# Sheet.net
KiCad netlist of a schematic drawn in Altium Designer
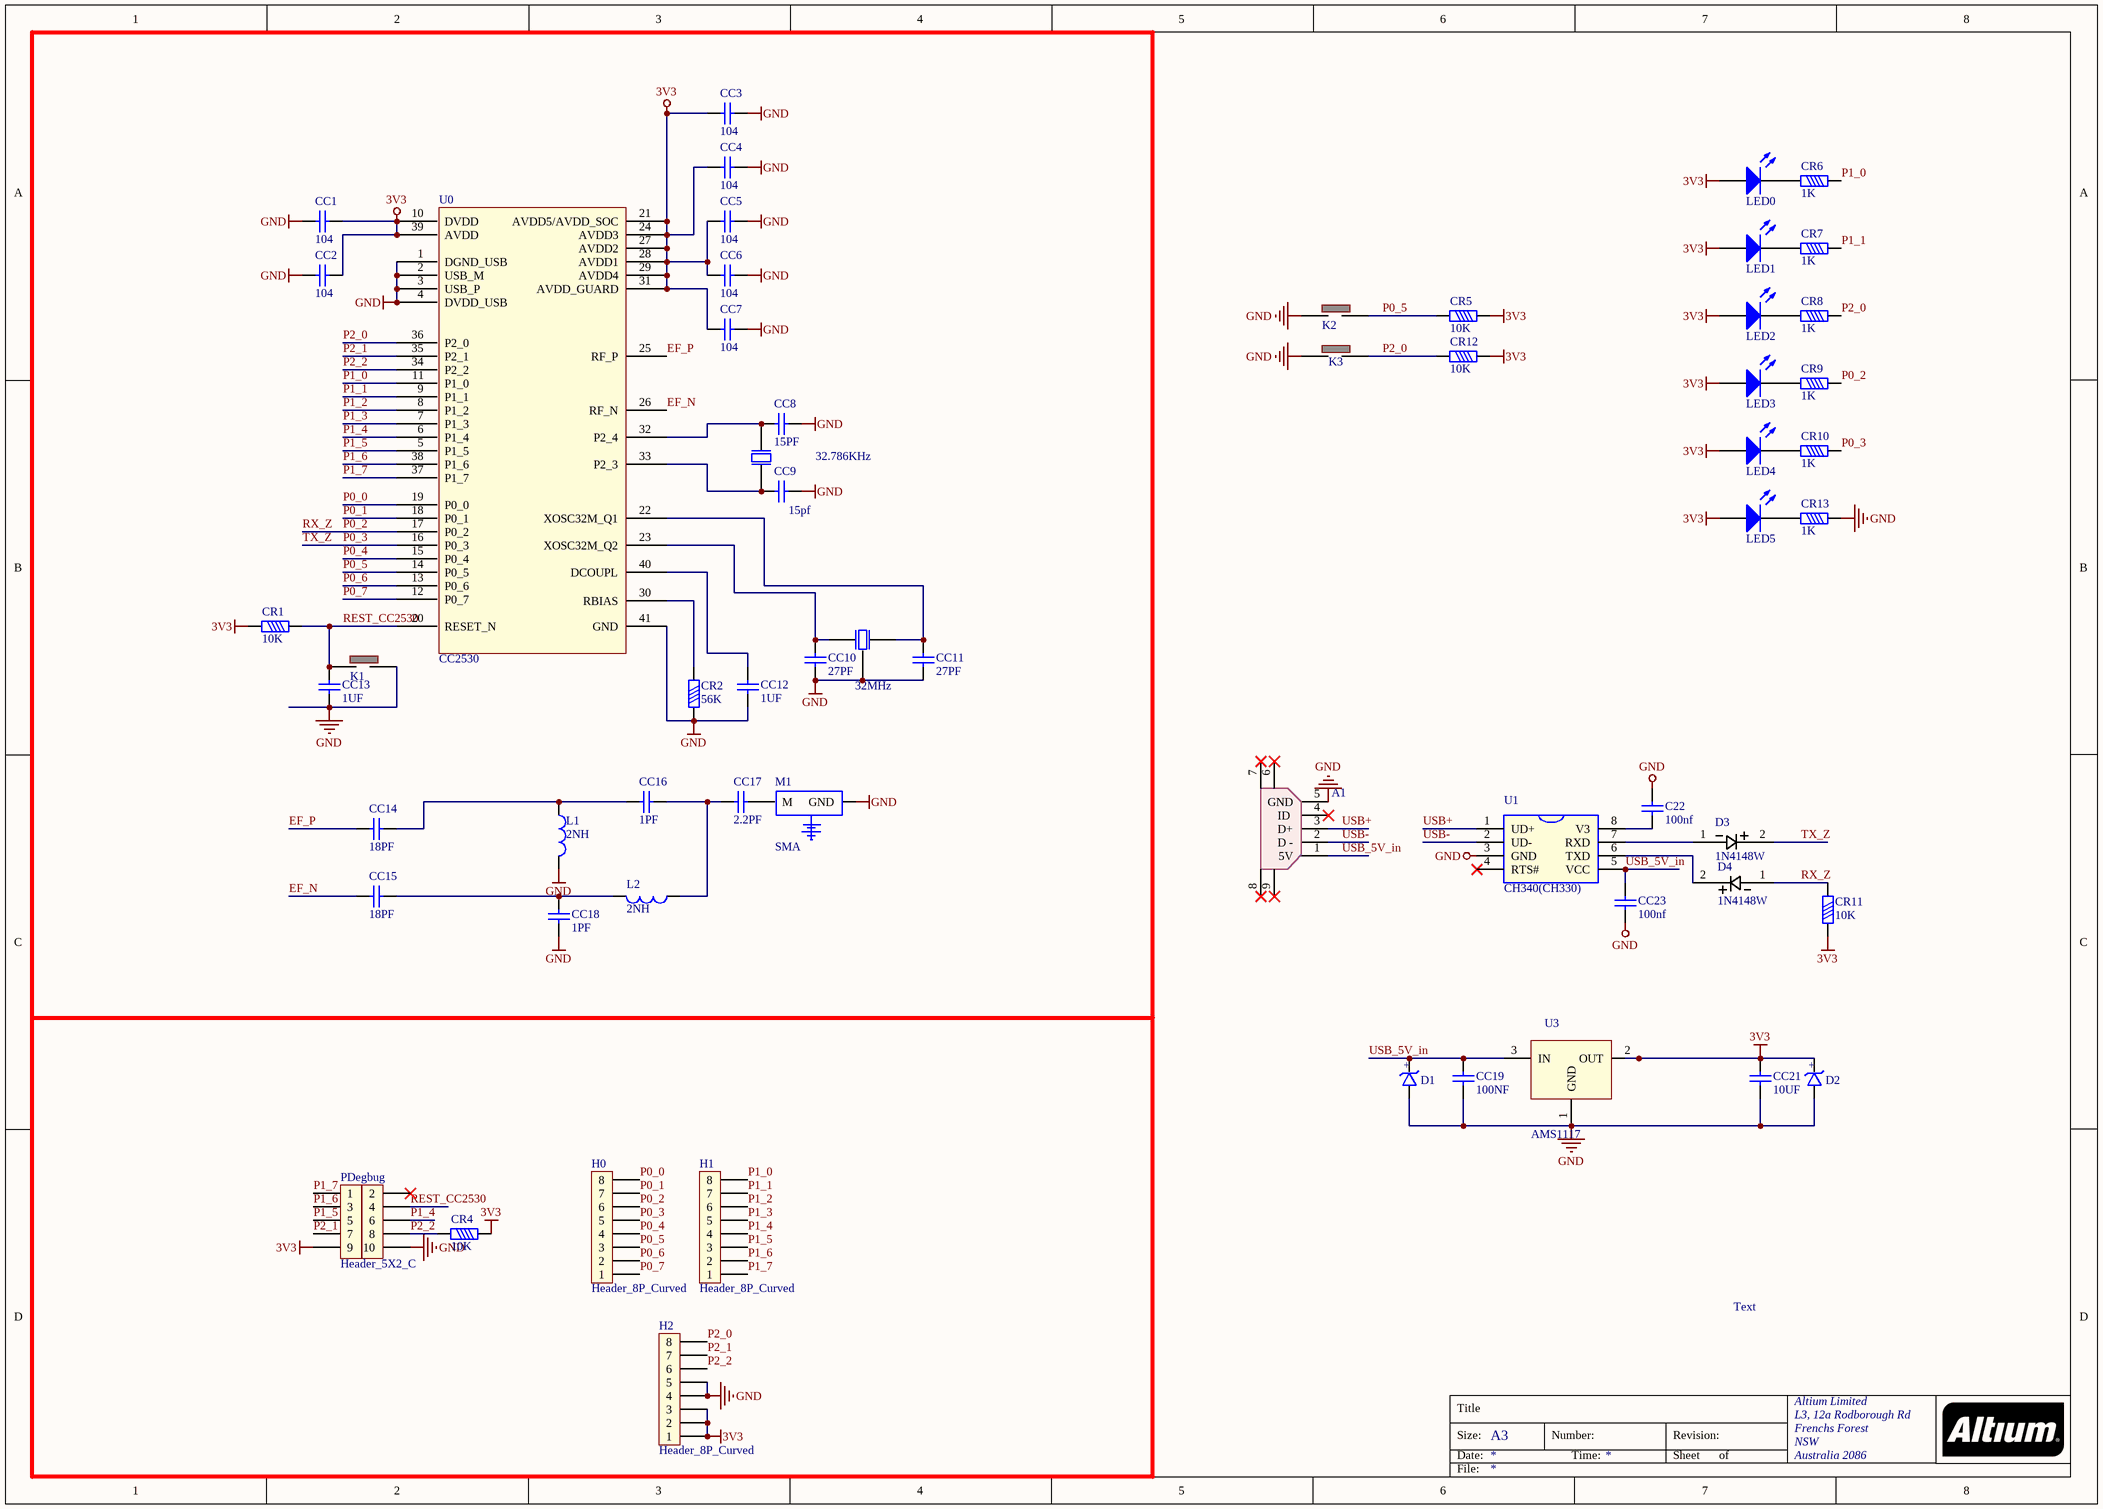
[diagram p0: Sheet.SchDoc]

(export (version "E")
  (design (tool "Eeschema 10.0.6"))
  (components
    (comp (ref "32.786KHz")
      (value "XTAL 3215 32.768kKHz")
      (footprint "T 3215")
      (libsource (lib "tianxiaohua_Schlib") (part "XTAL 3215 32.768kKHz"))
    )
    (comp (ref "32MHz")
      (value "XTAL 3225 8M")
      (footprint "T 3225")
      (libsource (lib "tianxiaohua_Schlib") (part "XTAL 3225 8M"))
    )
    (comp (ref "A1")
      (value "Micro USB")
      (footprint "Micro USB")
      (libsource (lib "tianxiaohua_Schlib") (part "Micro USB"))
    )
    (comp (ref "C22")
      (value "100nf")
      (footprint "CC1608-0603")
      (description "Polarized Capacitor (Radial)")
      (fields (field (name "Comment") "Cap Chip 0603") (field (name "PUBLISHER") "Altium Limited"))
      (libsource (lib "EButterflyIntegratedLibrary") (part "Cap Chip 0603"))
    )
    (comp (ref "CC1")
      (value "104")
      (footprint "CC1608-0603")
      (description "Polarized Capacitor (Radial)")
      (fields (field (name "Comment") "Cap Chip 0603") (field (name "PUBLISHER") "Altium Limited"))
      (libsource (lib "EButterflyIntegratedLibrary") (part "Cap Chip 0603"))
    )
    (comp (ref "CC2")
      (value "104")
      (footprint "CC1608-0603")
      (description "Polarized Capacitor (Radial)")
      (fields (field (name "Comment") "Cap Chip 0603") (field (name "PUBLISHER") "Altium Limited"))
      (libsource (lib "EButterflyIntegratedLibrary") (part "Cap Chip 0603"))
    )
    (comp (ref "CC3")
      (value "104")
      (footprint "CC1608-0603")
      (description "Polarized Capacitor (Radial)")
      (fields (field (name "Comment") "Cap Chip 0603") (field (name "PUBLISHER") "Altium Limited"))
      (libsource (lib "EButterflyIntegratedLibrary") (part "Cap Chip 0603"))
    )
    (comp (ref "CC4")
      (value "104")
      (footprint "CC1608-0603")
      (description "Polarized Capacitor (Radial)")
      (fields (field (name "Comment") "Cap Chip 0603") (field (name "PUBLISHER") "Altium Limited"))
      (libsource (lib "EButterflyIntegratedLibrary") (part "Cap Chip 0603"))
    )
    (comp (ref "CC5")
      (value "104")
      (footprint "CC1608-0603")
      (description "Polarized Capacitor (Radial)")
      (fields (field (name "Comment") "Cap Chip 0603") (field (name "PUBLISHER") "Altium Limited"))
      (libsource (lib "EButterflyIntegratedLibrary") (part "Cap Chip 0603"))
    )
    (comp (ref "CC6")
      (value "104")
      (footprint "CC1608-0603")
      (description "Polarized Capacitor (Radial)")
      (fields (field (name "Comment") "Cap Chip 0603") (field (name "PUBLISHER") "Altium Limited"))
      (libsource (lib "EButterflyIntegratedLibrary") (part "Cap Chip 0603"))
    )
    (comp (ref "CC7")
      (value "104")
      (footprint "CC1608-0603")
      (description "Polarized Capacitor (Radial)")
      (fields (field (name "Comment") "Cap Chip 0603") (field (name "PUBLISHER") "Altium Limited"))
      (libsource (lib "EButterflyIntegratedLibrary") (part "Cap Chip 0603"))
    )
    (comp (ref "CC8")
      (value "15PF")
      (footprint "CC1608-0603")
      (description "Polarized Capacitor (Radial)")
      (fields (field (name "Comment") "Cap Chip 0603") (field (name "PUBLISHER") "Altium Limited"))
      (libsource (lib "EButterflyIntegratedLibrary") (part "Cap Chip 0603"))
    )
    (comp (ref "CC9")
      (value "15pf")
      (footprint "CC1608-0603")
      (description "Polarized Capacitor (Radial)")
      (fields (field (name "Comment") "Cap Chip 0603") (field (name "PUBLISHER") "Altium Limited"))
      (libsource (lib "EButterflyIntegratedLibrary") (part "Cap Chip 0603"))
    )
    (comp (ref "CC10")
      (value "27PF")
      (footprint "CC1608-0603")
      (description "Polarized Capacitor (Radial)")
      (fields (field (name "Comment") "Cap Chip 0603") (field (name "PUBLISHER") "Altium Limited"))
      (libsource (lib "EButterflyIntegratedLibrary") (part "Cap Chip 0603"))
    )
    (comp (ref "CC11")
      (value "27PF")
      (footprint "CC1608-0603")
      (description "Polarized Capacitor (Radial)")
      (fields (field (name "Comment") "Cap Chip 0603") (field (name "PUBLISHER") "Altium Limited"))
      (libsource (lib "EButterflyIntegratedLibrary") (part "Cap Chip 0603"))
    )
    (comp (ref "CC12")
      (value "1UF")
      (footprint "CC1608-0603")
      (description "Polarized Capacitor (Radial)")
      (fields (field (name "Comment") "Cap Chip 0603") (field (name "PUBLISHER") "Altium Limited"))
      (libsource (lib "EButterflyIntegratedLibrary") (part "Cap Chip 0603"))
    )
    (comp (ref "CC13")
      (value "1UF")
      (footprint "CC1608-0603")
      (description "Polarized Capacitor (Radial)")
      (fields (field (name "Comment") "Cap Chip 0603") (field (name "PUBLISHER") "Altium Limited"))
      (libsource (lib "EButterflyIntegratedLibrary") (part "Cap Chip 0603"))
    )
    (comp (ref "CC14")
      (value "18PF")
      (footprint "CC1608-0603")
      (description "Polarized Capacitor (Radial)")
      (fields (field (name "Comment") "Cap Chip 0603") (field (name "PUBLISHER") "Altium Limited"))
      (libsource (lib "EButterflyIntegratedLibrary") (part "Cap Chip 0603"))
    )
    (comp (ref "CC15")
      (value "18PF")
      (footprint "CC1608-0603")
      (description "Polarized Capacitor (Radial)")
      (fields (field (name "Comment") "Cap Chip 0603") (field (name "PUBLISHER") "Altium Limited"))
      (libsource (lib "EButterflyIntegratedLibrary") (part "Cap Chip 0603"))
    )
    (comp (ref "CC16")
      (value "1PF")
      (footprint "CC1608-0603")
      (description "Polarized Capacitor (Radial)")
      (fields (field (name "Comment") "Cap Chip 0603") (field (name "PUBLISHER") "Altium Limited"))
      (libsource (lib "EButterflyIntegratedLibrary") (part "Cap Chip 0603"))
    )
    (comp (ref "CC17")
      (value "2.2PF")
      (footprint "CC1608-0603")
      (description "Polarized Capacitor (Radial)")
      (fields (field (name "Comment") "Cap Chip 0603") (field (name "PUBLISHER") "Altium Limited"))
      (libsource (lib "EButterflyIntegratedLibrary") (part "Cap Chip 0603"))
    )
    (comp (ref "CC18")
      (value "1PF")
      (footprint "CC1608-0603")
      (description "Polarized Capacitor (Radial)")
      (fields (field (name "Comment") "Cap Chip 0603") (field (name "PUBLISHER") "Altium Limited"))
      (libsource (lib "EButterflyIntegratedLibrary") (part "Cap Chip 0603"))
    )
    (comp (ref "CC19")
      (value "100NF")
      (footprint "CC1608-0603")
      (description "Polarized Capacitor (Radial)")
      (fields (field (name "Comment") "Cap Chip 0603") (field (name "PUBLISHER") "Altium Limited"))
      (libsource (lib "EButterflyIntegratedLibrary") (part "Cap Chip 0603"))
    )
    (comp (ref "CC21")
      (value "10UF")
      (footprint "CC1608-0603")
      (description "Polarized Capacitor (Radial)")
      (fields (field (name "Comment") "Cap Chip 0603") (field (name "PUBLISHER") "Altium Limited"))
      (libsource (lib "EButterflyIntegratedLibrary") (part "Cap Chip 0603"))
    )
    (comp (ref "CC23")
      (value "100nf")
      (footprint "CC1608-0603")
      (description "Polarized Capacitor (Radial)")
      (fields (field (name "Comment") "Cap Chip 0603") (field (name "PUBLISHER") "Altium Limited"))
      (libsource (lib "EButterflyIntegratedLibrary") (part "Cap Chip 0603"))
    )
    (comp (ref "CR1")
      (value "10K")
      (footprint "CR1608-0603")
      (description "Resistor")
      (fields (field (name "Comment") "Resistor Chip 0603") (field (name "PUBLISHER") "Altium Limited"))
      (libsource (lib "") (part "Resistor Chip 0603_1"))
    )
    (comp (ref "CR2")
      (value "56K")
      (footprint "CR1608-0603")
      (description "Resistor")
      (fields (field (name "Comment") "Resistor Chip 0603") (field (name "PUBLISHER") "Altium Limited"))
      (libsource (lib "EButterflyIntegratedLibrary") (part "Resistor Chip 0603"))
    )
    (comp (ref "CR4")
      (value "10K")
      (footprint "CR1608-0603")
      (description "Resistor")
      (fields (field (name "Comment") "Resistor Chip 0603") (field (name "PUBLISHER") "Altium Limited"))
      (libsource (lib "") (part "Resistor Chip 0603_1"))
    )
    (comp (ref "CR5")
      (value "10K")
      (footprint "CR1608-0603")
      (description "Resistor")
      (fields (field (name "Comment") "Resistor Chip 0603") (field (name "PUBLISHER") "Altium Limited"))
      (libsource (lib "") (part "Resistor Chip 0603_1"))
    )
    (comp (ref "CR6")
      (value "1K")
      (footprint "CR1608-0603")
      (description "Resistor")
      (fields (field (name "Comment") "Resistor Chip 0603") (field (name "PUBLISHER") "Altium Limited"))
      (libsource (lib "") (part "Resistor Chip 0603_1"))
    )
    (comp (ref "CR7")
      (value "1K")
      (footprint "CR1608-0603")
      (description "Resistor")
      (fields (field (name "Comment") "Resistor Chip 0603") (field (name "PUBLISHER") "Altium Limited"))
      (libsource (lib "") (part "Resistor Chip 0603_1"))
    )
    (comp (ref "CR8")
      (value "1K")
      (footprint "CR1608-0603")
      (description "Resistor")
      (fields (field (name "Comment") "Resistor Chip 0603") (field (name "PUBLISHER") "Altium Limited"))
      (libsource (lib "") (part "Resistor Chip 0603_1"))
    )
    (comp (ref "CR9")
      (value "1K")
      (footprint "CR1608-0603")
      (description "Resistor")
      (fields (field (name "Comment") "Resistor Chip 0603") (field (name "PUBLISHER") "Altium Limited"))
      (libsource (lib "") (part "Resistor Chip 0603_1"))
    )
    (comp (ref "CR10")
      (value "1K")
      (footprint "CR1608-0603")
      (description "Resistor")
      (fields (field (name "Comment") "Resistor Chip 0603") (field (name "PUBLISHER") "Altium Limited"))
      (libsource (lib "") (part "Resistor Chip 0603_1"))
    )
    (comp (ref "CR11")
      (value "10K")
      (footprint "CR1608-0603")
      (description "Resistor")
      (fields (field (name "Comment") "Resistor Chip 0603") (field (name "PUBLISHER") "Altium Limited"))
      (libsource (lib "EButterflyIntegratedLibrary") (part "Resistor Chip 0603"))
    )
    (comp (ref "CR12")
      (value "10K")
      (footprint "CR1608-0603")
      (description "Resistor")
      (fields (field (name "Comment") "Resistor Chip 0603") (field (name "PUBLISHER") "Altium Limited"))
      (libsource (lib "") (part "Resistor Chip 0603_1"))
    )
    (comp (ref "CR13")
      (value "1K")
      (footprint "CR1608-0603")
      (description "Resistor")
      (fields (field (name "Comment") "Resistor Chip 0603") (field (name "PUBLISHER") "Altium Limited"))
      (libsource (lib "") (part "Resistor Chip 0603_1"))
    )
    (comp (ref "D1")
      (value "SMBJ3.3A")
      (footprint "DO214AA(SMB)")
      (description "3.3V稳压管，缓解瞬间电压冲击")
      (libsource (lib "tianxiaohua_Schlib") (part "SMBJ3.3A"))
    )
    (comp (ref "D2")
      (value "SMBJ3.3A")
      (footprint "DO214AA(SMB)")
      (description "3.3V稳压管，缓解瞬间电压冲击")
      (libsource (lib "tianxiaohua_Schlib") (part "SMBJ3.3A"))
    )
    (comp (ref "D3")
      (value "1N4148W")
      (footprint "SOD-123")
      (description "开关二极管 贴片 1N4148W 1206/SOD-123 丝印T4 150MA 75V")
      (libsource (lib "tianxiaohua_Schlib") (part "1N4148W"))
    )
    (comp (ref "D4")
      (value "1N4148W")
      (footprint "SOD-123")
      (description "开关二极管 贴片 1N4148W 1206/SOD-123 丝印T4 150MA 75V")
      (libsource (lib "tianxiaohua_Schlib") (part "1N4148W"))
    )
    (comp (ref "H0")
      (value "Header_8P_Curved")
      (footprint "Header_2_54_8PW")
      (description "弯的8P排针")
      (libsource (lib "tianxiaohua_Schlib") (part "Header_8P_Curved"))
    )
    (comp (ref "H1")
      (value "Header_8P_Curved")
      (footprint "Header_2_54_8PW")
      (description "弯的8P排针")
      (libsource (lib "tianxiaohua_Schlib") (part "Header_8P_Curved"))
    )
    (comp (ref "H2")
      (value "Header_8P_Curved")
      (footprint "Header_2_54_8PW")
      (description "弯的8P排针")
      (libsource (lib "tianxiaohua_Schlib") (part "Header_8P_Curved"))
    )
    (comp (ref "K1")
      (value "KEY 3*4")
      (footprint "KEY 3*4")
      (libsource (lib "tianxiaohua_Schlib") (part "KEY 3*4"))
    )
    (comp (ref "K2")
      (value "KEY 3*4")
      (footprint "KEY 3*4")
      (libsource (lib "tianxiaohua_Schlib") (part "KEY 3*4"))
    )
    (comp (ref "K3")
      (value "KEY 3*4")
      (footprint "KEY 3*4")
      (libsource (lib "tianxiaohua_Schlib") (part "KEY 3*4"))
    )
    (comp (ref "L1")
      (value "2NH")
      (footprint "CR1608-0603")
      (description "Inductor")
      (fields (field (name "Comment") "Inductor Chip") (field (name "PUBLISHER") "Altium Limited"))
      (libsource (lib "EButterflyIntegratedLibrary") (part "Inductor Chip"))
    )
    (comp (ref "L2")
      (value "2NH")
      (footprint "CR1608-0603")
      (description "Inductor")
      (fields (field (name "Comment") "Inductor Chip") (field (name "PUBLISHER") "Altium Limited"))
      (libsource (lib "EButterflyIntegratedLibrary") (part "Inductor Chip"))
    )
    (comp (ref "LED0")
      (value "LED Chip")
      (footprint "CLED1608-0603")
      (description "Typical Chip LED")
      (fields (field (name "PUBLISHER") "Altium Limited"))
      (libsource (lib "EButterflyIntegratedLibrary") (part "LED Chip"))
    )
    (comp (ref "LED1")
      (value "LED Chip")
      (footprint "CLED1608-0603")
      (description "Typical Chip LED")
      (fields (field (name "PUBLISHER") "Altium Limited"))
      (libsource (lib "EButterflyIntegratedLibrary") (part "LED Chip"))
    )
    (comp (ref "LED2")
      (value "LED Chip")
      (footprint "CLED1608-0603")
      (description "Typical Chip LED")
      (fields (field (name "PUBLISHER") "Altium Limited"))
      (libsource (lib "EButterflyIntegratedLibrary") (part "LED Chip"))
    )
    (comp (ref "LED3")
      (value "LED Chip")
      (footprint "CLED1608-0603")
      (description "Typical Chip LED")
      (fields (field (name "PUBLISHER") "Altium Limited"))
      (libsource (lib "EButterflyIntegratedLibrary") (part "LED Chip"))
    )
    (comp (ref "LED4")
      (value "LED Chip")
      (footprint "CLED1608-0603")
      (description "Typical Chip LED")
      (fields (field (name "PUBLISHER") "Altium Limited"))
      (libsource (lib "EButterflyIntegratedLibrary") (part "LED Chip"))
    )
    (comp (ref "LED5")
      (value "LED Chip")
      (footprint "CLED1608-0603")
      (description "Typical Chip LED")
      (fields (field (name "PUBLISHER") "Altium Limited"))
      (libsource (lib "EButterflyIntegratedLibrary") (part "LED Chip"))
    )
    (comp (ref "M1")
      (value "SMA")
      (footprint "SMA-KE")
      (description "天线")
      (libsource (lib "tianxiaohua_Schlib") (part "SMA"))
    )
    (comp (ref "PDegbug")
      (value "Header_5X2_C")
      (footprint "Header_10_for_zigbee")
      (description "双排2*5弯排针")
      (libsource (lib "tianxiaohua_Schlib") (part "Header_5X2_C"))
    )
    (comp (ref "U0")
      (value "CC2530")
      (footprint "QLP40 (Reflow)")
      (description "Zigbee")
      (libsource (lib "tianxiaohua_Schlib") (part "CC2530"))
    )
    (comp (ref "U1")
      (value "CH340(CH330)")
      (footprint "SOP8")
      (description "USB转串口rs232的芯片，内置晶振")
      (libsource (lib "tianxiaohua_Schlib") (part "CH340(CH330)"))
    )
    (comp (ref "U3")
      (value "AMS1117")
      (footprint "SOT-223")
      (description "降压3.3V")
      (libsource (lib "tianxiaohua_Schlib") (part "AMS1117"))
    )
  )
  (nets
    (net (code "1") (name "/EF_N") (class "Default")
      (node (ref "CC15") (pin "2") (pinfunction "2_2") (pintype "passive"))
      (node (ref "U0") (pin "26") (pinfunction "RF_N_26") (pintype "passive"))
    )
    (net (code "2") (name "/EF_P") (class "Default")
      (node (ref "CC14") (pin "2") (pinfunction "2_2") (pintype "passive"))
      (node (ref "U0") (pin "25") (pinfunction "RF_P_25") (pintype "passive"))
    )
    (net (code "3") (name "/P0_0") (class "Default")
      (node (ref "H0") (pin "8") (pinfunction "8_8") (pintype "passive"))
      (node (ref "U0") (pin "19") (pinfunction "P0_0_19") (pintype "passive"))
    )
    (net (code "4") (name "/P0_1") (class "Default")
      (node (ref "H0") (pin "7") (pinfunction "7_7") (pintype "passive"))
      (node (ref "U0") (pin "18") (pinfunction "P0_1_18") (pintype "passive"))
    )
    (net (code "5") (name "/P0_2") (class "Default")
      (node (ref "CR11") (pin "2") (pinfunction "2_2") (pintype "passive"))
      (node (ref "CR9") (pin "1") (pinfunction "1_1") (pintype "passive"))
      (node (ref "D4") (pin "1") (pinfunction "1_1") (pintype "passive"))
      (node (ref "H0") (pin "6") (pinfunction "6_6") (pintype "passive"))
      (node (ref "U0") (pin "17") (pinfunction "P0_2_17") (pintype "passive"))
    )
    (net (code "6") (name "/P0_3") (class "Default")
      (node (ref "CR10") (pin "1") (pinfunction "1_1") (pintype "passive"))
      (node (ref "D3") (pin "2") (pinfunction "2_2") (pintype "passive"))
      (node (ref "H0") (pin "5") (pinfunction "5_5") (pintype "passive"))
      (node (ref "U0") (pin "16") (pinfunction "P0_3_16") (pintype "passive"))
    )
    (net (code "7") (name "/P0_4") (class "Default")
      (node (ref "H0") (pin "4") (pinfunction "4_4") (pintype "passive"))
      (node (ref "U0") (pin "15") (pinfunction "P0_4_15") (pintype "passive"))
    )
    (net (code "8") (name "/P0_5") (class "Default")
      (node (ref "CR5") (pin "2") (pinfunction "2_2") (pintype "passive"))
      (node (ref "H0") (pin "3") (pinfunction "3_3") (pintype "passive"))
      (node (ref "K2") (pin "2") (pinfunction "2_2") (pintype "passive"))
      (node (ref "U0") (pin "14") (pinfunction "P0_5_14") (pintype "passive"))
    )
    (net (code "9") (name "/P0_6") (class "Default")
      (node (ref "H0") (pin "2") (pinfunction "2_2") (pintype "passive"))
      (node (ref "U0") (pin "13") (pinfunction "P0_6_13") (pintype "passive"))
    )
    (net (code "10") (name "/P0_7") (class "Default")
      (node (ref "H0") (pin "1") (pinfunction "1_1") (pintype "passive"))
      (node (ref "U0") (pin "12") (pinfunction "P0_7_12") (pintype "passive"))
    )
    (net (code "11") (name "/P1_0") (class "Default")
      (node (ref "CR6") (pin "1") (pinfunction "1_1") (pintype "passive"))
      (node (ref "H1") (pin "8") (pinfunction "8_8") (pintype "passive"))
      (node (ref "U0") (pin "11") (pinfunction "P1_0_11") (pintype "passive"))
    )
    (net (code "12") (name "/P1_1") (class "Default")
      (node (ref "CR7") (pin "1") (pinfunction "1_1") (pintype "passive"))
      (node (ref "H1") (pin "7") (pinfunction "7_7") (pintype "passive"))
      (node (ref "U0") (pin "9") (pinfunction "P1_1_9") (pintype "passive"))
    )
    (net (code "13") (name "/P1_2") (class "Default")
      (node (ref "H1") (pin "6") (pinfunction "6_6") (pintype "passive"))
      (node (ref "U0") (pin "8") (pinfunction "P1_2_8") (pintype "passive"))
    )
    (net (code "14") (name "/P1_3") (class "Default")
      (node (ref "H1") (pin "5") (pinfunction "5_5") (pintype "passive"))
      (node (ref "U0") (pin "7") (pinfunction "P1_3_7") (pintype "passive"))
    )
    (net (code "15") (name "/P1_4") (class "Default")
      (node (ref "H1") (pin "4") (pinfunction "4_4") (pintype "passive"))
      (node (ref "PDegbug") (pin "6") (pinfunction "6_6") (pintype "passive"))
      (node (ref "U0") (pin "6") (pinfunction "P1_4_6") (pintype "passive"))
    )
    (net (code "16") (name "/P1_5") (class "Default")
      (node (ref "H1") (pin "3") (pinfunction "3_3") (pintype "passive"))
      (node (ref "PDegbug") (pin "5") (pinfunction "5_5") (pintype "passive"))
      (node (ref "U0") (pin "5") (pinfunction "P1_5_5") (pintype "passive"))
    )
    (net (code "17") (name "/P1_6") (class "Default")
      (node (ref "H1") (pin "2") (pinfunction "2_2") (pintype "passive"))
      (node (ref "PDegbug") (pin "3") (pinfunction "3_3") (pintype "passive"))
      (node (ref "U0") (pin "38") (pinfunction "P1_6_38") (pintype "passive"))
    )
    (net (code "18") (name "/P1_7") (class "Default")
      (node (ref "H1") (pin "1") (pinfunction "1_1") (pintype "passive"))
      (node (ref "PDegbug") (pin "1") (pinfunction "1_1") (pintype "passive"))
      (node (ref "U0") (pin "37") (pinfunction "P1_7_37") (pintype "passive"))
    )
    (net (code "19") (name "/P2_0") (class "Default")
      (node (ref "CR12") (pin "2") (pinfunction "2_2") (pintype "passive"))
      (node (ref "CR8") (pin "1") (pinfunction "1_1") (pintype "passive"))
      (node (ref "H2") (pin "8") (pinfunction "8_8") (pintype "passive"))
      (node (ref "K3") (pin "2") (pinfunction "2_2") (pintype "passive"))
      (node (ref "U0") (pin "36") (pinfunction "P2_0_36") (pintype "passive"))
    )
    (net (code "20") (name "/P2_1") (class "Default")
      (node (ref "H2") (pin "7") (pinfunction "7_7") (pintype "passive"))
      (node (ref "PDegbug") (pin "7") (pinfunction "7_7") (pintype "passive"))
      (node (ref "U0") (pin "35") (pinfunction "P2_1_35") (pintype "passive"))
    )
    (net (code "21") (name "/P2_2") (class "Default")
      (node (ref "CR4") (pin "2") (pinfunction "2_2") (pintype "passive"))
      (node (ref "H2") (pin "6") (pinfunction "6_6") (pintype "passive"))
      (node (ref "PDegbug") (pin "8") (pinfunction "8_8") (pintype "passive"))
      (node (ref "U0") (pin "34") (pinfunction "P2_2_34") (pintype "passive"))
    )
    (net (code "22") (name "/REST_CC2530") (class "Default")
      (node (ref "CC13") (pin "1") (pinfunction "1_1") (pintype "passive"))
      (node (ref "CR1") (pin "1") (pinfunction "1_1") (pintype "passive"))
      (node (ref "K1") (pin "1") (pinfunction "1_1") (pintype "passive"))
      (node (ref "PDegbug") (pin "4") (pinfunction "4_4") (pintype "passive"))
      (node (ref "U0") (pin "20") (pinfunction "RESET_N_20") (pintype "passive"))
    )
    (net (code "23") (name "/USB+") (class "Default")
      (node (ref "A1") (pin "3") (pinfunction "D+_3") (pintype "passive"))
      (node (ref "U1") (pin "1") (pinfunction "UD+_1") (pintype "passive"))
    )
    (net (code "24") (name "/USB-") (class "Default")
      (node (ref "A1") (pin "2") (pinfunction "D_-_2") (pintype "passive"))
      (node (ref "U1") (pin "2") (pinfunction "UD-_2") (pintype "passive"))
    )
    (net (code "25") (name "/USB_5V_in") (class "Default")
      (node (ref "A1") (pin "1") (pinfunction "5V_1") (pintype "passive"))
      (node (ref "CC19") (pin "1") (pinfunction "1_1") (pintype "passive"))
      (node (ref "CC23") (pin "2") (pinfunction "2_2") (pintype "passive"))
      (node (ref "D1") (pin "1") (pinfunction "1_1") (pintype "passive"))
      (node (ref "U1") (pin "5") (pinfunction "VCC_5") (pintype "passive"))
      (node (ref "U3") (pin "3") (pinfunction "IN_3") (pintype "passive"))
    )
    (net (code "26") (name "3V3") (class "Default")
      (node (ref "CC1") (pin "2") (pinfunction "2_2") (pintype "passive"))
      (node (ref "CC2") (pin "2") (pinfunction "2_2") (pintype "passive"))
      (node (ref "CC21") (pin "1") (pinfunction "1_1") (pintype "passive"))
      (node (ref "CC3") (pin "1") (pinfunction "1_1") (pintype "passive"))
      (node (ref "CC4") (pin "1") (pinfunction "1_1") (pintype "passive"))
      (node (ref "CC5") (pin "1") (pinfunction "1_1") (pintype "passive"))
      (node (ref "CC6") (pin "1") (pinfunction "1_1") (pintype "passive"))
      (node (ref "CC7") (pin "1") (pinfunction "1_1") (pintype "passive"))
      (node (ref "CR1") (pin "2") (pinfunction "2_2") (pintype "passive"))
      (node (ref "CR11") (pin "1") (pinfunction "1_1") (pintype "passive"))
      (node (ref "CR12") (pin "1") (pinfunction "1_1") (pintype "passive"))
      (node (ref "CR4") (pin "1") (pinfunction "1_1") (pintype "passive"))
      (node (ref "CR5") (pin "1") (pinfunction "1_1") (pintype "passive"))
      (node (ref "D2") (pin "1") (pinfunction "1_1") (pintype "passive"))
      (node (ref "H2") (pin "1") (pinfunction "1_1") (pintype "passive"))
      (node (ref "H2") (pin "2") (pinfunction "2_2") (pintype "passive"))
      (node (ref "H2") (pin "3") (pinfunction "3_3") (pintype "passive"))
      (node (ref "LED0") (pin "1") (pinfunction "A_1") (pintype "passive"))
      (node (ref "LED1") (pin "1") (pinfunction "A_1") (pintype "passive"))
      (node (ref "LED2") (pin "1") (pinfunction "A_1") (pintype "passive"))
      (node (ref "LED3") (pin "1") (pinfunction "A_1") (pintype "passive"))
      (node (ref "LED4") (pin "1") (pinfunction "A_1") (pintype "passive"))
      (node (ref "LED5") (pin "1") (pinfunction "A_1") (pintype "passive"))
      (node (ref "PDegbug") (pin "9") (pinfunction "9_9") (pintype "passive"))
      (node (ref "U0") (pin "10") (pinfunction "DVDD_10") (pintype "passive"))
      (node (ref "U0") (pin "21") (pinfunction "AVDD5/AVDD_SOC_21") (pintype "passive"))
      (node (ref "U0") (pin "24") (pinfunction "AVDD3_24") (pintype "passive"))
      (node (ref "U0") (pin "27") (pinfunction "AVDD2_27") (pintype "passive"))
      (node (ref "U0") (pin "28") (pinfunction "AVDD1_28") (pintype "passive"))
      (node (ref "U0") (pin "29") (pinfunction "AVDD4_29") (pintype "passive"))
      (node (ref "U0") (pin "31") (pinfunction "_AVDD_GUARD_31") (pintype "passive"))
      (node (ref "U0") (pin "39") (pinfunction "AVDD_39") (pintype "passive"))
      (node (ref "U3") (pin "2") (pinfunction "OUT_2") (pintype "passive"))
    )
    (net (code "27") (name "GND") (class "Default")
      (node (ref "32MHz") (pin "3") (pinfunction "GND_3") (pintype "passive"))
      (node (ref "A1") (pin "5") (pinfunction "GND_5") (pintype "passive"))
      (node (ref "C22") (pin "1") (pinfunction "1_1") (pintype "passive"))
      (node (ref "CC1") (pin "1") (pinfunction "1_1") (pintype "passive"))
      (node (ref "CC10") (pin "1") (pinfunction "1_1") (pintype "passive"))
      (node (ref "CC11") (pin "1") (pinfunction "1_1") (pintype "passive"))
      (node (ref "CC12") (pin "1") (pinfunction "1_1") (pintype "passive"))
      (node (ref "CC13") (pin "2") (pinfunction "2_2") (pintype "passive"))
      (node (ref "CC18") (pin "2") (pinfunction "2_2") (pintype "passive"))
      (node (ref "CC19") (pin "2") (pinfunction "2_2") (pintype "passive"))
      (node (ref "CC2") (pin "1") (pinfunction "1_1") (pintype "passive"))
      (node (ref "CC21") (pin "2") (pinfunction "2_2") (pintype "passive"))
      (node (ref "CC23") (pin "1") (pinfunction "1_1") (pintype "passive"))
      (node (ref "CC3") (pin "2") (pinfunction "2_2") (pintype "passive"))
      (node (ref "CC4") (pin "2") (pinfunction "2_2") (pintype "passive"))
      (node (ref "CC5") (pin "2") (pinfunction "2_2") (pintype "passive"))
      (node (ref "CC6") (pin "2") (pinfunction "2_2") (pintype "passive"))
      (node (ref "CC7") (pin "2") (pinfunction "2_2") (pintype "passive"))
      (node (ref "CC8") (pin "2") (pinfunction "2_2") (pintype "passive"))
      (node (ref "CC9") (pin "2") (pinfunction "2_2") (pintype "passive"))
      (node (ref "CR13") (pin "1") (pinfunction "1_1") (pintype "passive"))
      (node (ref "CR2") (pin "1") (pinfunction "1_1") (pintype "passive"))
      (node (ref "D1") (pin "2") (pinfunction "2_2") (pintype "passive"))
      (node (ref "D2") (pin "2") (pinfunction "2_2") (pintype "passive"))
      (node (ref "H2") (pin "4") (pinfunction "4_4") (pintype "passive"))
      (node (ref "H2") (pin "5") (pinfunction "5_5") (pintype "passive"))
      (node (ref "K1") (pin "2") (pinfunction "2_2") (pintype "passive"))
      (node (ref "K2") (pin "1") (pinfunction "1_1") (pintype "passive"))
      (node (ref "K3") (pin "1") (pinfunction "1_1") (pintype "passive"))
      (node (ref "L1") (pin "2") (pinfunction "2_2") (pintype "passive"))
      (node (ref "M1") (pin "2") (pinfunction "GND_2") (pintype "passive"))
      (node (ref "PDegbug") (pin "10") (pinfunction "10_10") (pintype "passive"))
      (node (ref "U0") (pin "1") (pinfunction "DGND_USB_1") (pintype "passive"))
      (node (ref "U0") (pin "2") (pinfunction "USB_M_2") (pintype "passive"))
      (node (ref "U0") (pin "3") (pinfunction "USB_P_3") (pintype "passive"))
      (node (ref "U0") (pin "4") (pinfunction "DVDD_USB_4") (pintype "passive"))
      (node (ref "U0") (pin "41") (pinfunction "GND_41") (pintype "passive"))
      (node (ref "U1") (pin "3") (pinfunction "GND_3") (pintype "passive"))
      (node (ref "U3") (pin "1") (pinfunction "GND_1") (pintype "passive"))
    )
    (net (code "28") (name "Net-(32.786KHz-OSC1)") (class "Default")
      (node (ref "32.786KHz") (pin "1") (pinfunction "OSC1_1") (pintype "passive"))
      (node (ref "CC9") (pin "1") (pinfunction "1_1") (pintype "passive"))
      (node (ref "U0") (pin "33") (pinfunction "P2_3_33") (pintype "passive"))
    )
    (net (code "29") (name "Net-(32.786KHz-OSC2)") (class "Default")
      (node (ref "32.786KHz") (pin "2") (pinfunction "OSC2_2") (pintype "passive"))
      (node (ref "CC8") (pin "1") (pinfunction "1_1") (pintype "passive"))
      (node (ref "U0") (pin "32") (pinfunction "P2_4_32") (pintype "passive"))
    )
    (net (code "30") (name "Net-(32MHz-OSC1)") (class "Default")
      (node (ref "32MHz") (pin "1") (pinfunction "OSC1_1") (pintype "passive"))
      (node (ref "CC10") (pin "2") (pinfunction "2_2") (pintype "passive"))
      (node (ref "U0") (pin "23") (pinfunction "XOSC32M_Q2_23") (pintype "passive"))
    )
    (net (code "31") (name "Net-(32MHz-OSC2)") (class "Default")
      (node (ref "32MHz") (pin "2") (pinfunction "OSC2_2") (pintype "passive"))
      (node (ref "CC11") (pin "2") (pinfunction "2_2") (pintype "passive"))
      (node (ref "U0") (pin "22") (pinfunction "XOSC32M_Q1_22") (pintype "passive"))
    )
    (net (code "32") (name "Net-(CC14-Pad1)") (class "Default")
      (node (ref "CC14") (pin "1") (pinfunction "1_1") (pintype "passive"))
      (node (ref "CC16") (pin "1") (pinfunction "1_1") (pintype "passive"))
      (node (ref "L1") (pin "1") (pinfunction "1_1") (pintype "passive"))
    )
    (net (code "33") (name "Net-(CC15-Pad1)") (class "Default")
      (node (ref "CC15") (pin "1") (pinfunction "1_1") (pintype "passive"))
      (node (ref "CC18") (pin "1") (pinfunction "1_1") (pintype "passive"))
      (node (ref "L2") (pin "2") (pinfunction "2_2") (pintype "passive"))
    )
    (net (code "34") (name "Net-(CC16-Pad2)") (class "Default")
      (node (ref "CC16") (pin "2") (pinfunction "2_2") (pintype "passive"))
      (node (ref "CC17") (pin "1") (pinfunction "1_1") (pintype "passive"))
      (node (ref "L2") (pin "1") (pinfunction "1_1") (pintype "passive"))
    )
    (net (code "35") (name "Net-(LED0-K)") (class "Default")
      (node (ref "CR6") (pin "2") (pinfunction "2_2") (pintype "passive"))
      (node (ref "LED0") (pin "2") (pinfunction "K_2") (pintype "passive"))
    )
    (net (code "36") (name "Net-(LED1-K)") (class "Default")
      (node (ref "CR7") (pin "2") (pinfunction "2_2") (pintype "passive"))
      (node (ref "LED1") (pin "2") (pinfunction "K_2") (pintype "passive"))
    )
    (net (code "37") (name "Net-(LED2-K)") (class "Default")
      (node (ref "CR8") (pin "2") (pinfunction "2_2") (pintype "passive"))
      (node (ref "LED2") (pin "2") (pinfunction "K_2") (pintype "passive"))
    )
    (net (code "38") (name "Net-(LED3-K)") (class "Default")
      (node (ref "CR9") (pin "2") (pinfunction "2_2") (pintype "passive"))
      (node (ref "LED3") (pin "2") (pinfunction "K_2") (pintype "passive"))
    )
    (net (code "39") (name "Net-(LED4-K)") (class "Default")
      (node (ref "CR10") (pin "2") (pinfunction "2_2") (pintype "passive"))
      (node (ref "LED4") (pin "2") (pinfunction "K_2") (pintype "passive"))
    )
    (net (code "40") (name "Net-(LED5-K)") (class "Default")
      (node (ref "CR13") (pin "2") (pinfunction "2_2") (pintype "passive"))
      (node (ref "LED5") (pin "2") (pinfunction "K_2") (pintype "passive"))
    )
    (net (code "41") (name "Net-(M1-M)") (class "Default")
      (node (ref "CC17") (pin "2") (pinfunction "2_2") (pintype "passive"))
      (node (ref "M1") (pin "1") (pinfunction "M_1") (pintype "passive"))
    )
    (net (code "42") (name "Net-(U0-DCOUPL)") (class "Default")
      (node (ref "CC12") (pin "2") (pinfunction "2_2") (pintype "passive"))
      (node (ref "U0") (pin "40") (pinfunction "DCOUPL_40") (pintype "passive"))
    )
    (net (code "43") (name "Net-(U0-RBIAS)") (class "Default")
      (node (ref "CR2") (pin "2") (pinfunction "2_2") (pintype "passive"))
      (node (ref "U0") (pin "30") (pinfunction "RBIAS_30") (pintype "passive"))
    )
    (net (code "44") (name "Net-(U1-RXD)") (class "Default")
      (node (ref "D3") (pin "1") (pinfunction "1_1") (pintype "passive"))
      (node (ref "U1") (pin "7") (pinfunction "RXD_7") (pintype "passive"))
    )
    (net (code "45") (name "Net-(U1-TXD)") (class "Default")
      (node (ref "D4") (pin "2") (pinfunction "2_2") (pintype "passive"))
      (node (ref "U1") (pin "6") (pinfunction "TXD_6") (pintype "passive"))
    )
    (net (code "46") (name "Net-(U1-V3)") (class "Default")
      (node (ref "C22") (pin "2") (pinfunction "2_2") (pintype "passive"))
      (node (ref "U1") (pin "8") (pinfunction "V3_8") (pintype "passive"))
    )
    (net (code "47") (name "unconnected-(A1-ID-Pad4)") (class "Default")
      (node (ref "A1") (pin "4") (pinfunction "ID_4") (pintype "passive+no_connect"))
    )
    (net (code "48") (name "unconnected-(A1-Pad6)") (class "Default")
      (node (ref "A1") (pin "6") (pinfunction "6_6") (pintype "passive+no_connect"))
    )
    (net (code "49") (name "unconnected-(A1-Pad7)") (class "Default")
      (node (ref "A1") (pin "7") (pinfunction "7_7") (pintype "passive+no_connect"))
    )
    (net (code "50") (name "unconnected-(A1-Pad8)") (class "Default")
      (node (ref "A1") (pin "8") (pinfunction "8_8") (pintype "passive+no_connect"))
    )
    (net (code "51") (name "unconnected-(A1-Pad9)") (class "Default")
      (node (ref "A1") (pin "9") (pinfunction "9_9") (pintype "passive+no_connect"))
    )
    (net (code "52") (name "unconnected-(PDegbug-Pad2)") (class "Default")
      (node (ref "PDegbug") (pin "2") (pinfunction "2_2") (pintype "passive+no_connect"))
    )
    (net (code "53") (name "unconnected-(U1-RTS#-Pad4)") (class "Default")
      (node (ref "U1") (pin "4") (pinfunction "RTS#_4") (pintype "passive+no_connect"))
    )
  )
)
